# screw_and_Hole.net
KiCad netlist of a schematic drawn in Altium Designer
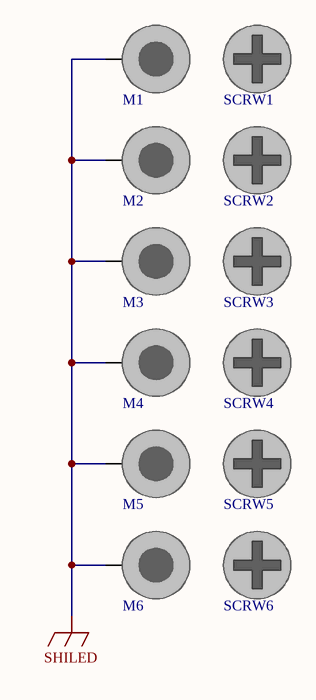
[diagram p0: screw and Hole.SchDoc]

(export (version "E")
  (design (tool "Eeschema 10.0.6"))
  (components
    (comp (ref "M1")
      (value "DNP/MH")
      (footprint "SCMH_M2")
      (description "SCREW mouting, M2, 2.0mm diameter and 4.0mm PanHead")
      (libsource (lib "mech_mountingHole") (part "SCMH_M2"))
    )
    (comp (ref "M2")
      (value "DNP/MH")
      (footprint "SCMH_M2")
      (description "SCREW mouting, M2, 2.0mm diameter and 4.0mm PanHead")
      (libsource (lib "mech_mountingHole") (part "SCMH_M2"))
    )
    (comp (ref "M3")
      (value "DNP/MH")
      (footprint "SCMH_M2")
      (description "SCREW mouting, M2, 2.0mm diameter and 4.0mm PanHead")
      (libsource (lib "mech_mountingHole") (part "SCMH_M2"))
    )
    (comp (ref "M4")
      (value "DNP/MH")
      (footprint "SCMH_M2")
      (description "SCREW mouting, M2, 2.0mm diameter and 4.0mm PanHead")
      (libsource (lib "mech_mountingHole") (part "SCMH_M2"))
    )
    (comp (ref "M5")
      (value "DNP/MH")
      (footprint "SCMH_M2")
      (description "SCREW mouting, M2, 2.0mm diameter and 4.0mm PanHead")
      (libsource (lib "mech_mountingHole") (part "SCMH_M2"))
    )
    (comp (ref "M6")
      (value "DNP/MH")
      (footprint "SCMH_M2")
      (description "SCREW mouting, M2, 2.0mm diameter and 4.0mm PanHead")
      (libsource (lib "mech_mountingHole") (part "SCMH_M2"))
    )
    (comp (ref "SCRW1")
      (value "SCREW")
      (footprint "SCRW_CHSH_PHLIPS_M2X4")
      (description "SCREW, M2, 2.0mm diameter and 4.0mm PanHead")
      (libsource (lib "mech_mountingHole") (part "SCRW_CHSH_PHLIPS_M2X4"))
    )
    (comp (ref "SCRW2")
      (value "SCREW")
      (footprint "SCRW_CHSH_PHLIPS_M2X4")
      (description "SCREW, M2, 2.0mm diameter and 4.0mm PanHead")
      (libsource (lib "mech_mountingHole") (part "SCRW_CHSH_PHLIPS_M2X4"))
    )
    (comp (ref "SCRW3")
      (value "SCREW")
      (footprint "SCRW_CHSH_PHLIPS_M2X4")
      (description "SCREW, M2, 2.0mm diameter and 4.0mm PanHead")
      (libsource (lib "mech_mountingHole") (part "SCRW_CHSH_PHLIPS_M2X4"))
    )
    (comp (ref "SCRW4")
      (value "SCREW")
      (footprint "SCRW_CHSH_PHLIPS_M2X4")
      (description "SCREW, M2, 2.0mm diameter and 4.0mm PanHead")
      (libsource (lib "mech_mountingHole") (part "SCRW_CHSH_PHLIPS_M2X4"))
    )
    (comp (ref "SCRW5")
      (value "SCREW")
      (footprint "SCRW_CHSH_PHLIPS_M2X4")
      (description "SCREW, M2, 2.0mm diameter and 4.0mm PanHead")
      (libsource (lib "mech_mountingHole") (part "SCRW_CHSH_PHLIPS_M2X4"))
    )
    (comp (ref "SCRW6")
      (value "SCREW")
      (footprint "SCRW_CHSH_PHLIPS_M2X4")
      (description "SCREW, M2, 2.0mm diameter and 4.0mm PanHead")
      (libsource (lib "mech_mountingHole") (part "SCRW_CHSH_PHLIPS_M2X4"))
    )
  )
  (nets
    (net (code "1") (name "SHILED") (class "Default")
      (node (ref "M1") (pin "1") (pinfunction "1_1") (pintype "passive"))
      (node (ref "M2") (pin "1") (pinfunction "1_1") (pintype "passive"))
      (node (ref "M3") (pin "1") (pinfunction "1_1") (pintype "passive"))
      (node (ref "M4") (pin "1") (pinfunction "1_1") (pintype "passive"))
      (node (ref "M5") (pin "1") (pinfunction "1_1") (pintype "passive"))
      (node (ref "M6") (pin "1") (pinfunction "1_1") (pintype "passive"))
    )
  )
)
